# HGD_Sensor_v0_1_-20200807.net
KiCad netlist of a schematic drawn in Altium Designer
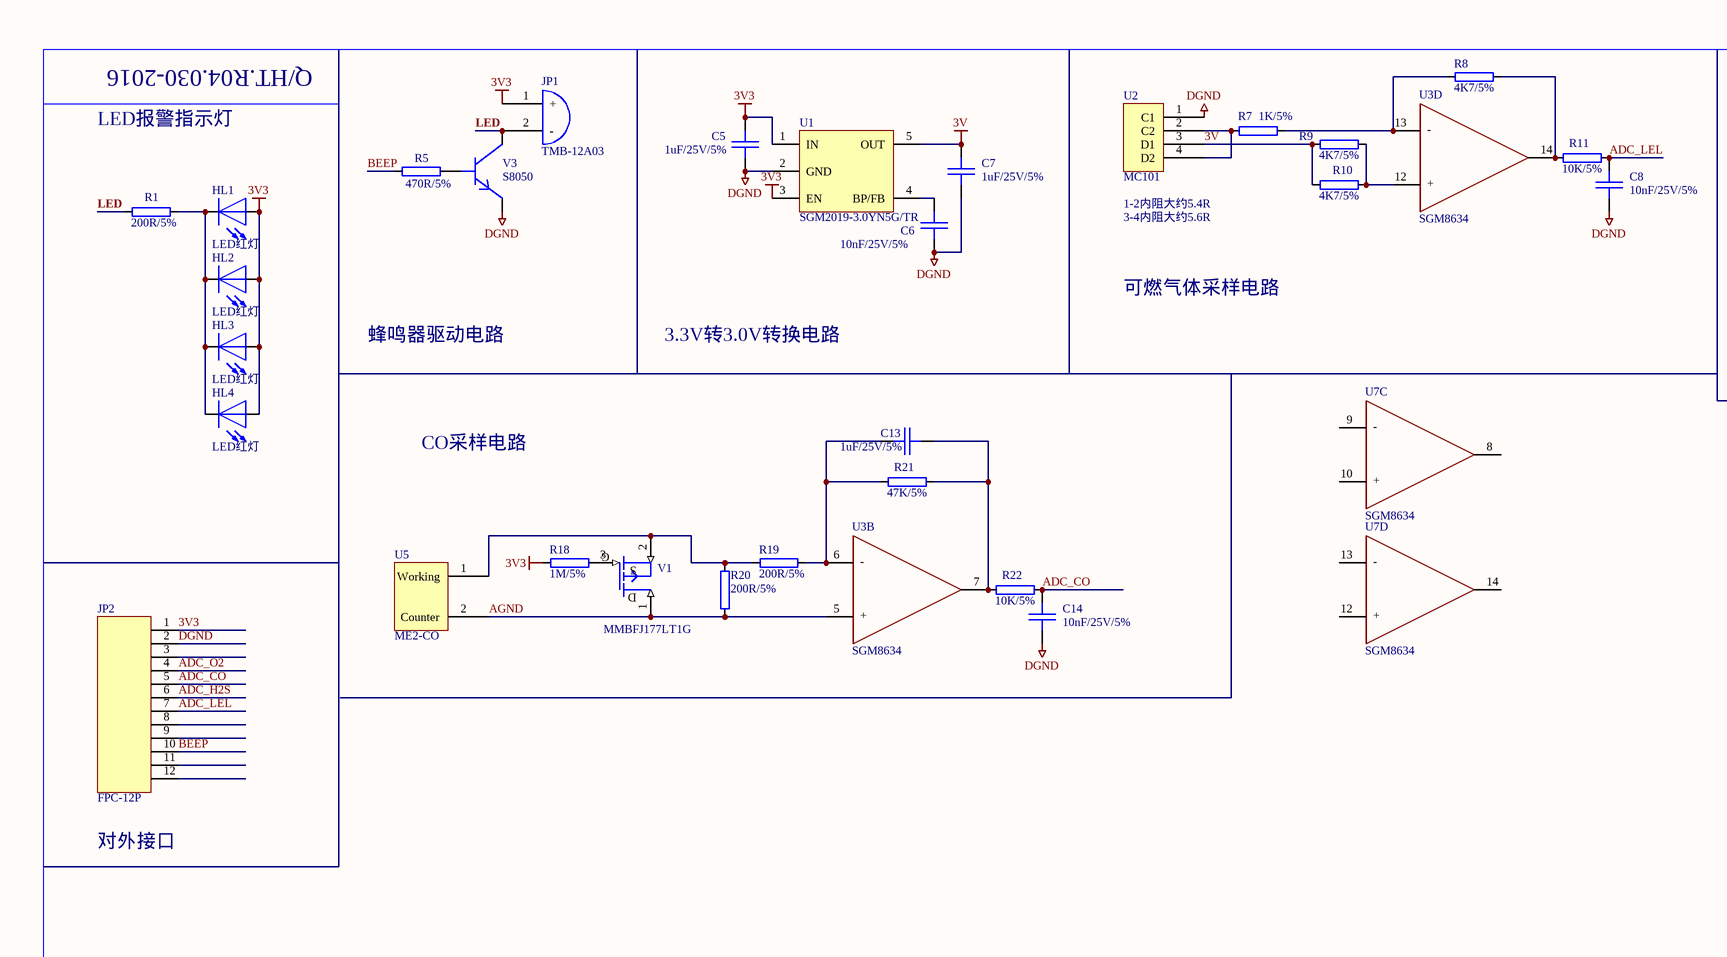
[diagram p0: HGD_Sensor(v0.1)-20200807.SchDoc, top left]
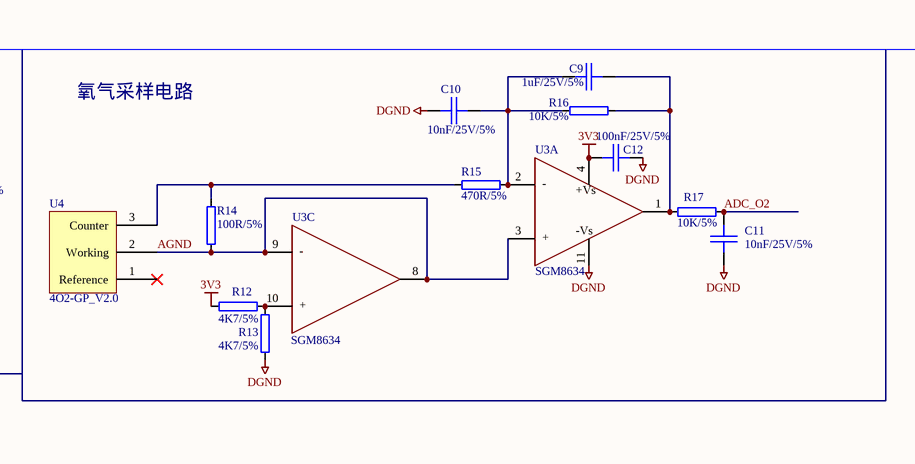
[diagram p1: HGD_Sensor(v0.1)-20200807.SchDoc, top right]
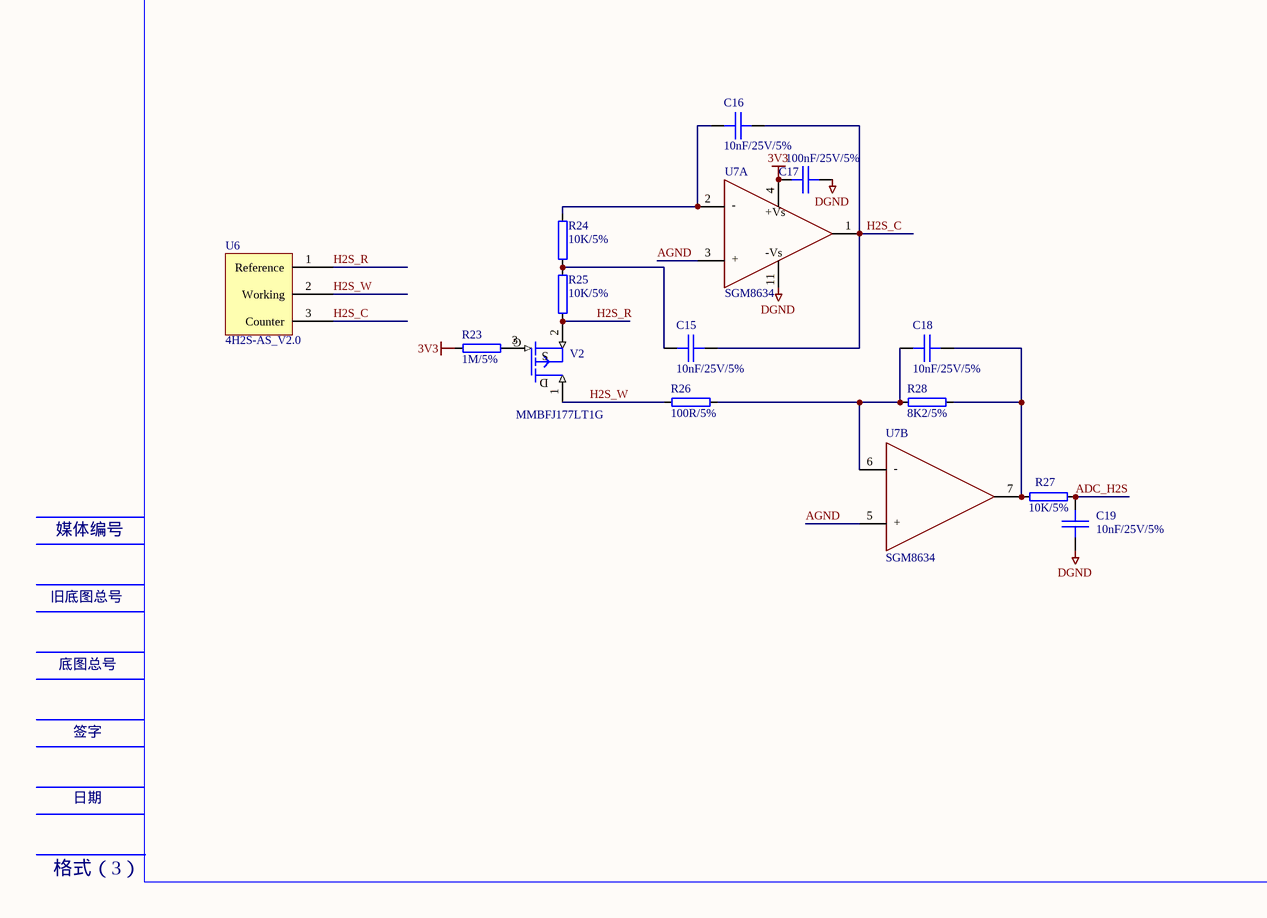
[diagram p2: HGD_Sensor(v0.1)-20200807.SchDoc, bottom left]
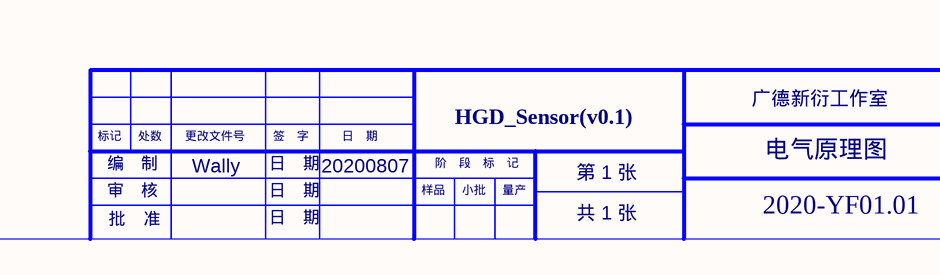
[diagram p3: HGD_Sensor(v0.1)-20200807.SchDoc, bottom right]

(export (version "E")
  (design (tool "Eeschema 10.0.6"))
  (components
    (comp (ref "C5")
      (value "1uF/25V/5%")
      (footprint "0805")
      (description "电容")
      (libsource (lib "*") (part "CAP"))
    )
    (comp (ref "C6")
      (value "10nF/25V/5%")
      (footprint "C0603")
      (description "电容")
      (libsource (lib "*") (part "CAP"))
    )
    (comp (ref "C7")
      (value "1uF/25V/5%")
      (footprint "0805")
      (description "电容")
      (libsource (lib "*") (part "CAP"))
    )
    (comp (ref "C8")
      (value "10nF/25V/5%")
      (footprint "C0603")
      (description "电容")
      (libsource (lib "*") (part "CAP"))
    )
    (comp (ref "C9")
      (value "1uF/25V/5%")
      (footprint "0805")
      (description "电容")
      (libsource (lib "*") (part "CAP"))
    )
    (comp (ref "C10")
      (value "10nF/25V/5%")
      (footprint "C0603")
      (description "电容")
      (libsource (lib "*") (part "CAP"))
    )
    (comp (ref "C11")
      (value "10nF/25V/5%")
      (footprint "C0603")
      (description "电容")
      (libsource (lib "*") (part "CAP"))
    )
    (comp (ref "C12")
      (value "100nF/25V/5%")
      (footprint "C0603")
      (description "电容")
      (libsource (lib "*") (part "CAP"))
    )
    (comp (ref "C13")
      (value "1uF/25V/5%")
      (footprint "0805")
      (description "电容")
      (libsource (lib "*") (part "CAP"))
    )
    (comp (ref "C14")
      (value "10nF/25V/5%")
      (footprint "C0603")
      (description "电容")
      (libsource (lib "*") (part "CAP"))
    )
    (comp (ref "C15")
      (value "10nF/25V/5%")
      (footprint "C0603")
      (description "电容")
      (libsource (lib "*") (part "CAP"))
    )
    (comp (ref "C16")
      (value "10nF/25V/5%")
      (footprint "C0603")
      (description "电容")
      (libsource (lib "*") (part "CAP"))
    )
    (comp (ref "C17")
      (value "100nF/25V/5%")
      (footprint "C0603")
      (description "电容")
      (libsource (lib "*") (part "CAP"))
    )
    (comp (ref "C18")
      (value "10nF/25V/5%")
      (footprint "C0603")
      (description "电容")
      (libsource (lib "*") (part "CAP"))
    )
    (comp (ref "C19")
      (value "10nF/25V/5%")
      (footprint "C0603")
      (description "电容")
      (libsource (lib "*") (part "CAP"))
    )
    (comp (ref "HL1")
      (value "LED红灯")
      (footprint "LED-3MM")
      (description "发光二极管")
      (libsource (lib "wypPCB_Lib") (part "发光二极管"))
    )
    (comp (ref "HL2")
      (value "LED红灯")
      (footprint "LED-3MM")
      (description "发光二极管")
      (libsource (lib "wypPCB_Lib") (part "发光二极管"))
    )
    (comp (ref "HL3")
      (value "LED红灯")
      (footprint "LED-3MM")
      (description "发光二极管")
      (libsource (lib "wypPCB_Lib") (part "发光二极管"))
    )
    (comp (ref "HL4")
      (value "LED红灯")
      (footprint "LED-3MM")
      (description "发光二极管")
      (libsource (lib "wypPCB_Lib") (part "发光二极管"))
    )
    (comp (ref "JP1")
      (value "TMB-12A03")
      (footprint "TMB-12A03")
      (description "TMB-12A03：3.3V有源蜂鸣器")
      (libsource (lib "wypPCB_Lib") (part "TMB-12A03"))
    )
    (comp (ref "JP2")
      (value "FPC-12P")
      (footprint "FPC-1.0MM-12P-W")
      (libsource (lib "wypPCB_Lib") (part "FPC-12P"))
    )
    (comp (ref "R1")
      (value "200R/5%")
      (footprint "R0603")
      (description "电阻")
      (libsource (lib "*") (part "RES2"))
    )
    (comp (ref "R5")
      (value "470R/5%")
      (footprint "R0603")
      (description "电阻")
      (libsource (lib "*") (part "RES2"))
    )
    (comp (ref "R7")
      (value "1K/5%")
      (footprint "R0603")
      (description "电阻")
      (libsource (lib "*") (part "RES2"))
    )
    (comp (ref "R8")
      (value "4K7/5%")
      (footprint "R0603")
      (description "电阻")
      (libsource (lib "*") (part "RES2"))
    )
    (comp (ref "R9")
      (value "4K7/5%")
      (footprint "R0603")
      (description "电阻")
      (libsource (lib "*") (part "RES2"))
    )
    (comp (ref "R10")
      (value "4K7/5%")
      (footprint "R0603")
      (description "电阻")
      (libsource (lib "*") (part "RES2"))
    )
    (comp (ref "R11")
      (value "10K/5%")
      (footprint "R0603")
      (description "电阻")
      (libsource (lib "*") (part "RES2"))
    )
    (comp (ref "R12")
      (value "4K7/5%")
      (footprint "R0603")
      (description "电阻")
      (libsource (lib "*") (part "RES2"))
    )
    (comp (ref "R13")
      (value "4K7/5%")
      (footprint "R0603")
      (description "电阻")
      (libsource (lib "*") (part "RES2"))
    )
    (comp (ref "R14")
      (value "100R/5%")
      (footprint "R0603")
      (description "电阻")
      (libsource (lib "*") (part "RES2"))
    )
    (comp (ref "R15")
      (value "470R/5%")
      (footprint "R0603")
      (description "电阻")
      (libsource (lib "*") (part "RES2"))
    )
    (comp (ref "R16")
      (value "10K/5%")
      (footprint "R0603")
      (description "电阻")
      (libsource (lib "*") (part "RES2"))
    )
    (comp (ref "R17")
      (value "10K/5%")
      (footprint "R0603")
      (description "电阻")
      (libsource (lib "*") (part "RES2"))
    )
    (comp (ref "R18")
      (value "1M/5%")
      (footprint "R0603")
      (description "电阻")
      (libsource (lib "*") (part "RES2"))
    )
    (comp (ref "R19")
      (value "200R/5%")
      (footprint "R0603")
      (description "电阻")
      (libsource (lib "*") (part "RES2"))
    )
    (comp (ref "R20")
      (value "200R/5%")
      (footprint "R0603")
      (description "电阻")
      (libsource (lib "*") (part "RES2"))
    )
    (comp (ref "R21")
      (value "47K/5%")
      (footprint "R0603")
      (description "电阻")
      (libsource (lib "*") (part "RES2"))
    )
    (comp (ref "R22")
      (value "10K/5%")
      (footprint "R0603")
      (description "电阻")
      (libsource (lib "*") (part "RES2"))
    )
    (comp (ref "R23")
      (value "1M/5%")
      (footprint "R0603")
      (description "电阻")
      (libsource (lib "*") (part "RES2"))
    )
    (comp (ref "R24")
      (value "10K/5%")
      (footprint "R0603")
      (description "电阻")
      (libsource (lib "*") (part "RES2"))
    )
    (comp (ref "R25")
      (value "10K/5%")
      (footprint "R0603")
      (description "电阻")
      (libsource (lib "*") (part "RES2"))
    )
    (comp (ref "R26")
      (value "100R/5%")
      (footprint "R0603")
      (description "电阻")
      (libsource (lib "*") (part "RES2"))
    )
    (comp (ref "R27")
      (value "10K/5%")
      (footprint "R0603")
      (description "电阻")
      (libsource (lib "*") (part "RES2"))
    )
    (comp (ref "R28")
      (value "8K2/5%")
      (footprint "R0603")
      (description "电阻")
      (libsource (lib "*") (part "RES2"))
    )
    (comp (ref "U1")
      (value "SGM2019-3.0YN5G/TR")
      (footprint "SGM2019_SOT23-5_95P280X125-5N")
      (description "SGM2019：Low Power, Low Dropout, RF Linear Regulators")
      (libsource (lib "wypPCB_Lib") (part "SGM2019"))
    )
    (comp (ref "U2")
      (value "MC101")
      (footprint "MC101")
      (description "MC101：可燃气体传感器")
      (libsource (lib "wypPCB_Lib") (part "MC101"))
    )
    (comp (ref "U3")
      (value "SGM8634")
      (footprint "SGM8634_TSSOP14_65P640X120-14N")
      (description "SGM8634：470μA, 6MHz, Rail-to-Rail I/O, CMOS Operational Amplifier")
      (libsource (lib "wypPCB_Lib") (part "SGM8634"))
    )
    (comp (ref "U4")
      (value "4O2-GP_V2.0")
      (footprint "4O2-GP_V2.0-1.5K-3.2*2.5*5.8")
      (description "4O2-GP_V2.0：O2传感器")
      (libsource (lib "wypPCB_Lib") (part "4O2-GP_V2.0"))
    )
    (comp (ref "U5")
      (value "ME2-CO")
      (footprint "ME2-CO_1.5K-3.2*2.5*5.8")
      (description "ME2-CO：CO传感器")
      (libsource (lib "wypPCB_Lib") (part "ME2-CO"))
    )
    (comp (ref "U6")
      (value "4H2S-AS_V2.0")
      (footprint "4H2S-AS_V2.0-1.5K-3.0*2.5*5.8")
      (description "4H2S-AS_V2.0：H2S传感器")
      (libsource (lib "wypPCB_Lib") (part "4H2S-AS_V2.0"))
    )
    (comp (ref "U7")
      (value "SGM8634")
      (footprint "SGM8634_TSSOP14_65P640X120-14N")
      (description "SGM8634：470μA, 6MHz, Rail-to-Rail I/O, CMOS Operational Amplifier")
      (libsource (lib "wypPCB_Lib") (part "SGM8634"))
    )
    (comp (ref "V1")
      (value "MMBFJ177LT1G")
      (footprint "MMBFJ177LT1G_SOT-23")
      (description "MMBFJ177LT1G：P-JFET?Chopper")
      (libsource (lib "wypPCB_Lib") (part "MMBFJ177LT1G"))
    )
    (comp (ref "V2")
      (value "MMBFJ177LT1G")
      (footprint "MMBFJ177LT1G_SOT-23")
      (description "MMBFJ177LT1G：P-JFET?Chopper")
      (libsource (lib "wypPCB_Lib") (part "MMBFJ177LT1G"))
    )
    (comp (ref "V3")
      (value "S8050")
      (footprint "SOT-23")
      (description "NPN三极管")
      (libsource (lib "ESLIB(v1.1)-AD9-20150731") (part "NPN"))
    )
  )
  (nets
    (net (code "1") (name "/ADC_CO") (class "Default")
      (node (ref "C14") (pin "1") (pintype "passive"))
      (node (ref "JP2") (pin "5") (pintype "passive"))
      (node (ref "R22") (pin "1") (pintype "passive"))
    )
    (net (code "2") (name "/ADC_H2S") (class "Default")
      (node (ref "C19") (pin "1") (pintype "passive"))
      (node (ref "JP2") (pin "6") (pintype "passive"))
      (node (ref "R27") (pin "2") (pintype "passive"))
    )
    (net (code "3") (name "/ADC_LEL") (class "Default")
      (node (ref "C8") (pin "1") (pintype "passive"))
      (node (ref "JP2") (pin "7") (pintype "passive"))
      (node (ref "R11") (pin "1") (pintype "passive"))
    )
    (net (code "4") (name "/ADC_O2") (class "Default")
      (node (ref "C11") (pin "1") (pintype "passive"))
      (node (ref "JP2") (pin "4") (pintype "passive"))
      (node (ref "R17") (pin "1") (pintype "passive"))
    )
    (net (code "5") (name "/AGND") (class "Default")
      (node (ref "R14") (pin "1") (pintype "passive"))
      (node (ref "R20") (pin "2") (pintype "passive"))
      (node (ref "U3") (pin "3") (pinfunction "+_3") (pintype "passive"))
      (node (ref "U3") (pin "5") (pinfunction "+_5") (pintype "passive"))
      (node (ref "U3") (pin "8") (pintype "passive"))
      (node (ref "U3") (pin "9") (pinfunction "-_9") (pintype "passive"))
      (node (ref "U4") (pin "2") (pinfunction "Working_2") (pintype "passive"))
      (node (ref "U5") (pin "2") (pinfunction "Counter_2") (pintype "passive"))
      (node (ref "U7") (pin "3") (pinfunction "+_3") (pintype "passive"))
      (node (ref "U7") (pin "5") (pinfunction "+_5") (pintype "passive"))
      (node (ref "V1") (pin "1") (pinfunction "D_1") (pintype "input"))
    )
    (net (code "6") (name "/BEEP") (class "Default")
      (node (ref "JP2") (pin "10") (pintype "passive"))
      (node (ref "R5") (pin "1") (pintype "passive"))
    )
    (net (code "7") (name "/H2S_C") (class "Default")
      (node (ref "C15") (pin "1") (pintype "passive"))
      (node (ref "C16") (pin "2") (pintype "passive"))
      (node (ref "U6") (pin "3") (pinfunction "Counter_3") (pintype "passive"))
      (node (ref "U7") (pin "1") (pintype "passive"))
    )
    (net (code "8") (name "/H2S_R") (class "Default")
      (node (ref "R25") (pin "2") (pintype "passive"))
      (node (ref "U6") (pin "1") (pinfunction "Reference_1") (pintype "passive"))
      (node (ref "V2") (pin "2") (pinfunction "S_2") (pintype "input"))
    )
    (net (code "9") (name "/H2S_W") (class "Default")
      (node (ref "R26") (pin "1") (pintype "passive"))
      (node (ref "U6") (pin "2") (pinfunction "Working_2") (pintype "passive"))
      (node (ref "V2") (pin "1") (pinfunction "D_1") (pintype "input"))
    )
    (net (code "10") (name "/LED") (class "Default")
      (node (ref "JP1") (pin "2") (pinfunction "-_2") (pintype "passive"))
      (node (ref "R1") (pin "2") (pintype "passive"))
      (node (ref "V3") (pin "C") (pintype "passive"))
    )
    (net (code "11") (name "3V") (class "Default")
      (node (ref "C7") (pin "1") (pintype "passive"))
      (node (ref "R10") (pin "2") (pintype "passive"))
      (node (ref "R9") (pin "2") (pintype "passive"))
      (node (ref "U1") (pin "5") (pinfunction "OUT_5") (pintype "passive"))
      (node (ref "U2") (pin "3") (pinfunction "D1_3") (pintype "passive"))
    )
    (net (code "12") (name "3V3") (class "Default")
      (node (ref "C12") (pin "2") (pintype "passive"))
      (node (ref "C17") (pin "2") (pintype "passive"))
      (node (ref "C5") (pin "1") (pintype "passive"))
      (node (ref "HL1") (pin "A") (pintype "passive"))
      (node (ref "HL2") (pin "A") (pintype "passive"))
      (node (ref "HL3") (pin "A") (pintype "passive"))
      (node (ref "HL4") (pin "A") (pintype "passive"))
      (node (ref "JP1") (pin "1") (pinfunction "+_1") (pintype "passive"))
      (node (ref "JP2") (pin "1") (pintype "passive"))
      (node (ref "R12") (pin "2") (pintype "passive"))
      (node (ref "R18") (pin "2") (pintype "passive"))
      (node (ref "R23") (pin "2") (pintype "passive"))
      (node (ref "U1") (pin "1") (pinfunction "IN_1") (pintype "passive"))
      (node (ref "U1") (pin "3") (pinfunction "EN_3") (pintype "passive"))
      (node (ref "U3") (pin "4") (pinfunction "+Vs_4") (pintype "passive"))
      (node (ref "U7") (pin "4") (pinfunction "+Vs_4") (pintype "passive"))
    )
    (net (code "13") (name "DGND") (class "Default")
      (node (ref "C10") (pin "2") (pintype "passive"))
      (node (ref "C11") (pin "2") (pintype "passive"))
      (node (ref "C12") (pin "1") (pintype "passive"))
      (node (ref "C14") (pin "2") (pintype "passive"))
      (node (ref "C17") (pin "1") (pintype "passive"))
      (node (ref "C19") (pin "2") (pintype "passive"))
      (node (ref "C5") (pin "2") (pintype "passive"))
      (node (ref "C6") (pin "2") (pintype "passive"))
      (node (ref "C7") (pin "2") (pintype "passive"))
      (node (ref "C8") (pin "2") (pintype "passive"))
      (node (ref "JP2") (pin "2") (pintype "passive"))
      (node (ref "R13") (pin "2") (pintype "passive"))
      (node (ref "U1") (pin "2") (pinfunction "GND_2") (pintype "passive"))
      (node (ref "U2") (pin "1") (pinfunction "C1_1") (pintype "passive"))
      (node (ref "U3") (pin "11") (pinfunction "-Vs_11") (pintype "passive"))
      (node (ref "U7") (pin "11") (pinfunction "-Vs_11") (pintype "passive"))
      (node (ref "V3") (pin "E") (pintype "passive"))
    )
    (net (code "14") (name "Net-(C9-Pad2)") (class "Default")
      (node (ref "C9") (pin "2") (pintype "passive"))
      (node (ref "R16") (pin "1") (pintype "passive"))
      (node (ref "R17") (pin "2") (pintype "passive"))
      (node (ref "U3") (pin "1") (pintype "passive"))
    )
    (net (code "15") (name "Net-(C13-Pad2)") (class "Default")
      (node (ref "C13") (pin "2") (pintype "passive"))
      (node (ref "R21") (pin "2") (pintype "passive"))
      (node (ref "R22") (pin "2") (pintype "passive"))
      (node (ref "U3") (pin "7") (pintype "passive"))
    )
    (net (code "16") (name "Net-(C15-Pad2)") (class "Default")
      (node (ref "C15") (pin "2") (pintype "passive"))
      (node (ref "R24") (pin "2") (pintype "passive"))
      (node (ref "R25") (pin "1") (pintype "passive"))
    )
    (net (code "17") (name "Net-(C18-Pad1)") (class "Default")
      (node (ref "C18") (pin "1") (pintype "passive"))
      (node (ref "R27") (pin "1") (pintype "passive"))
      (node (ref "R28") (pin "2") (pintype "passive"))
      (node (ref "U7") (pin "7") (pintype "passive"))
    )
    (net (code "18") (name "Net-(HL1-PadK)") (class "Default")
      (node (ref "HL1") (pin "K") (pintype "passive"))
      (node (ref "HL2") (pin "K") (pintype "passive"))
      (node (ref "HL3") (pin "K") (pintype "passive"))
      (node (ref "HL4") (pin "K") (pintype "passive"))
      (node (ref "R1") (pin "1") (pintype "passive"))
    )
    (net (code "19") (name "Net-(R5-Pad2)") (class "Default")
      (node (ref "R5") (pin "2") (pintype "passive"))
      (node (ref "V3") (pin "B") (pintype "passive"))
    )
    (net (code "20") (name "Net-(R11-Pad2)") (class "Default")
      (node (ref "R11") (pin "2") (pintype "passive"))
      (node (ref "R8") (pin "1") (pintype "passive"))
      (node (ref "U3") (pin "14") (pintype "passive"))
    )
    (net (code "21") (name "Net-(U1-BP{slash}FB)") (class "Default")
      (node (ref "C6") (pin "1") (pintype "passive"))
      (node (ref "U1") (pin "4") (pinfunction "BP/FB_4") (pintype "passive"))
    )
    (net (code "22") (name "Net-(U2-C2)") (class "Default")
      (node (ref "R7") (pin "2") (pintype "passive"))
      (node (ref "U2") (pin "2") (pinfunction "C2_2") (pintype "passive"))
      (node (ref "U2") (pin "4") (pinfunction "D2_4") (pintype "passive"))
    )
    (net (code "23") (name "Net-(U3A--)") (class "Default")
      (node (ref "C10") (pin "1") (pintype "passive"))
      (node (ref "C9") (pin "1") (pintype "passive"))
      (node (ref "R15") (pin "2") (pintype "passive"))
      (node (ref "R16") (pin "2") (pintype "passive"))
      (node (ref "U3") (pin "2") (pinfunction "-_2") (pintype "passive"))
    )
    (net (code "24") (name "Net-(U3B--)") (class "Default")
      (node (ref "C13") (pin "1") (pintype "passive"))
      (node (ref "R19") (pin "1") (pintype "passive"))
      (node (ref "R21") (pin "1") (pintype "passive"))
      (node (ref "U3") (pin "6") (pinfunction "-_6") (pintype "passive"))
    )
    (net (code "25") (name "Net-(U3C-+)") (class "Default")
      (node (ref "R12") (pin "1") (pintype "passive"))
      (node (ref "R13") (pin "1") (pintype "passive"))
      (node (ref "U3") (pin "10") (pinfunction "+_10") (pintype "passive"))
    )
    (net (code "26") (name "Net-(U3D-+)") (class "Default")
      (node (ref "R10") (pin "1") (pintype "passive"))
      (node (ref "R9") (pin "1") (pintype "passive"))
      (node (ref "U3") (pin "12") (pinfunction "+_12") (pintype "passive"))
    )
    (net (code "27") (name "Net-(U3D--)") (class "Default")
      (node (ref "R7") (pin "1") (pintype "passive"))
      (node (ref "R8") (pin "2") (pintype "passive"))
      (node (ref "U3") (pin "13") (pinfunction "-_13") (pintype "passive"))
    )
    (net (code "28") (name "Net-(U4-Counter)") (class "Default")
      (node (ref "R14") (pin "2") (pintype "passive"))
      (node (ref "R15") (pin "1") (pintype "passive"))
      (node (ref "U4") (pin "3") (pinfunction "Counter_3") (pintype "passive"))
    )
    (net (code "29") (name "Net-(U5-Working)") (class "Default")
      (node (ref "R19") (pin "2") (pintype "passive"))
      (node (ref "R20") (pin "1") (pintype "passive"))
      (node (ref "U5") (pin "1") (pinfunction "Working_1") (pintype "passive"))
      (node (ref "V1") (pin "2") (pinfunction "S_2") (pintype "input"))
    )
    (net (code "30") (name "Net-(U7A--)") (class "Default")
      (node (ref "C16") (pin "1") (pintype "passive"))
      (node (ref "R24") (pin "1") (pintype "passive"))
      (node (ref "U7") (pin "2") (pinfunction "-_2") (pintype "passive"))
    )
    (net (code "31") (name "Net-(U7B--)") (class "Default")
      (node (ref "C18") (pin "2") (pintype "passive"))
      (node (ref "R26") (pin "2") (pintype "passive"))
      (node (ref "R28") (pin "1") (pintype "passive"))
      (node (ref "U7") (pin "6") (pinfunction "-_6") (pintype "passive"))
    )
    (net (code "32") (name "Net-(V1-G)") (class "Default")
      (node (ref "R18") (pin "1") (pintype "passive"))
      (node (ref "V1") (pin "3") (pinfunction "G_3") (pintype "input"))
    )
    (net (code "33") (name "Net-(V2-G)") (class "Default")
      (node (ref "R23") (pin "1") (pintype "passive"))
      (node (ref "V2") (pin "3") (pinfunction "G_3") (pintype "input"))
    )
    (net (code "34") (name "unconnected-(JP2-Pad3)") (class "Default")
      (node (ref "JP2") (pin "3") (pintype "passive"))
    )
    (net (code "35") (name "unconnected-(JP2-Pad8)") (class "Default")
      (node (ref "JP2") (pin "8") (pintype "passive"))
    )
    (net (code "36") (name "unconnected-(JP2-Pad9)") (class "Default")
      (node (ref "JP2") (pin "9") (pintype "passive"))
    )
    (net (code "37") (name "unconnected-(JP2-Pad11)") (class "Default")
      (node (ref "JP2") (pin "11") (pintype "passive"))
    )
    (net (code "38") (name "unconnected-(JP2-Pad12)") (class "Default")
      (node (ref "JP2") (pin "12") (pintype "passive"))
    )
    (net (code "39") (name "unconnected-(U4-Reference-Pad1)") (class "Default")
      (node (ref "U4") (pin "1") (pinfunction "Reference_1") (pintype "passive+no_connect"))
    )
    (net (code "40") (name "unconnected-(U7-Pad8)") (class "Default")
      (node (ref "U7") (pin "8") (pintype "passive"))
    )
    (net (code "41") (name "unconnected-(U7-Pad14)") (class "Default")
      (node (ref "U7") (pin "14") (pintype "passive"))
    )
    (net (code "42") (name "unconnected-(U7C-+-Pad10)") (class "Default")
      (node (ref "U7") (pin "10") (pinfunction "+_10") (pintype "passive"))
    )
    (net (code "43") (name "unconnected-(U7C---Pad9)") (class "Default")
      (node (ref "U7") (pin "9") (pinfunction "-_9") (pintype "passive"))
    )
    (net (code "44") (name "unconnected-(U7D-+-Pad12)") (class "Default")
      (node (ref "U7") (pin "12") (pinfunction "+_12") (pintype "passive"))
    )
    (net (code "45") (name "unconnected-(U7D---Pad13)") (class "Default")
      (node (ref "U7") (pin "13") (pinfunction "-_13") (pintype "passive"))
    )
  )
)
